# PG14__Ethernet.net
KiCad netlist of a schematic drawn in Altium Designer
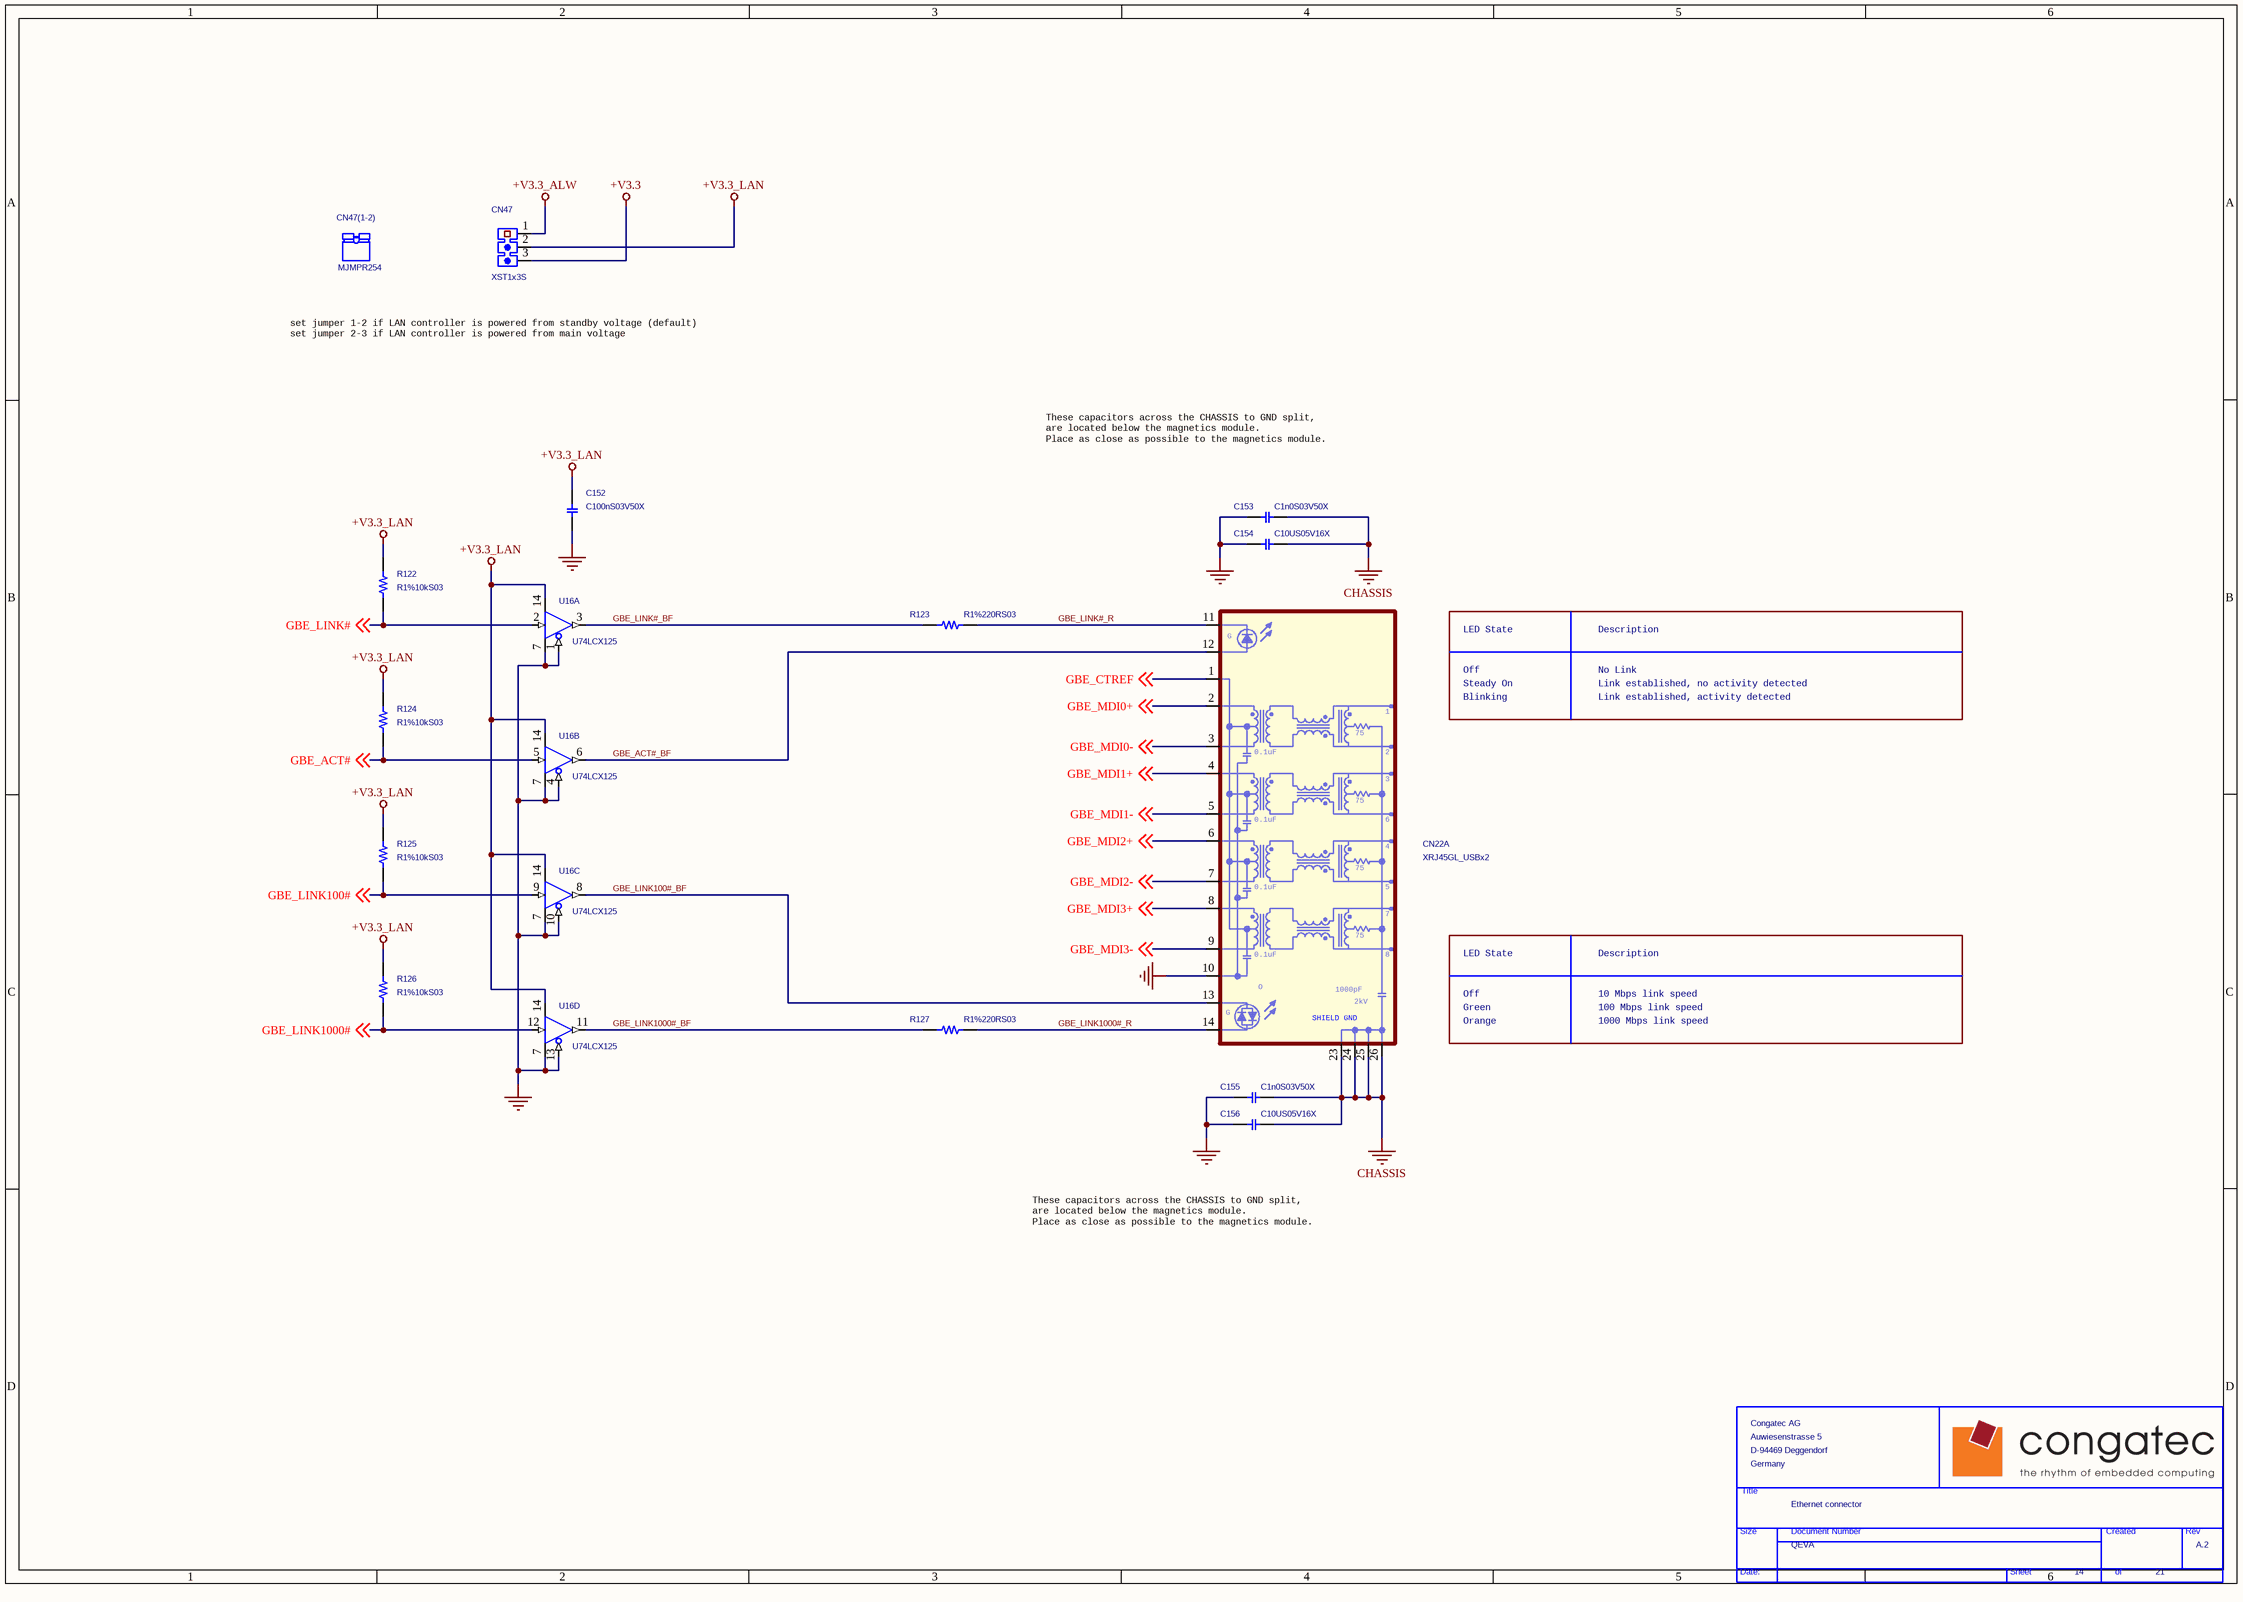
[diagram p0: PG14_ Ethernet.SchDoc]

(export (version "E")
  (design (tool "Eeschema 10.0.6"))
  (components
    (comp (ref "C152")
      (value "C100nS03V50X")
      (description "CAP 0.1U 50V +-10% SMD 0603 X7R WO/Pb")
      (fields
        (field (name "MANUFACTURE PART NUMBER") "C1608X7R1H104KT223858615649")
        (field (name "TOLERANCE") "10%")
      )
      (libsource (lib "*") (part "11_C_0"))
    )
    (comp (ref "C153")
      (value "C1n0S03V50X")
      (description "CAP 1000pF 50V 10% 0603 MLCC")
      (fields (field (name "PART NUMBER") "1124510290") (field (name "TOLERANCE") "10%"))
      (libsource (lib "*") (part "11_C_0"))
    )
    (comp (ref "C154")
      (value "C10US05V16X")
      (description "CAP 10u 6.3V +/-10% SMD 0805 MLCC X5R KEMET")
      (fields (field (name "MANUFACTURE PART NUMBER") "C0805C106K9PAC") (field (name "TOLERANCE") "10%"))
      (libsource (lib "*") (part "11_C_0"))
    )
    (comp (ref "C155")
      (value "C1n0S03V50X")
      (description "CAP 1000pF 50V 10% 0603 MLCC")
      (fields (field (name "PART NUMBER") "1124510290") (field (name "TOLERANCE") "10%"))
      (libsource (lib "*") (part "11_C_0"))
    )
    (comp (ref "C156")
      (value "C10US05V16X")
      (description "CAP 10u 6.3V +/-10% SMD 0805 MLCC X5R KEMET")
      (fields (field (name "MANUFACTURE PART NUMBER") "C0805C106K9PAC") (field (name "TOLERANCE") "10%"))
      (libsource (lib "*") (part "11_C_0"))
    )
    (comp (ref "CN22")
      (value "XRJ45GL_USBx2")
      (description "PhoneJack RJ45+USB*2 90D(F) W/LED&XFMR DIP")
      (fields (field (name "PART NUMBER") "165250820M") (field (name "PART_NUMBER") "41500328"))
      (libsource (lib "*") (part "1652_RJ45-P3515619W9_0"))
    )
    (comp (ref "CN47")
      (value "XST1x3S")
      (description "PIN HEADER 3*1P 180D(M) 2.54mm DIP WO/Pb")
      (fields
        (field (name "PART NUMBER") "1653003100")
        (field (name "MANUFACTURE PART NUMBER") "205-1x3GS RoHS1130-000-03S21N12564-03S10B-01G-6/3")
      )
      (libsource (lib "*") (part "1653_JH3X1V_0"))
    )
    (comp (ref "CN47(1-2)")
      (value "MJMPR254")
      (description "MINI JUMPER 2P 180D(F) 2.54mm DIP (yellow)")
      (fields
        (field (name "MANUFACTURE PART NUMBER") "1132-040-02HL0305302MJ1P-BG0L151-240-00000306")
        (field (name "PART NUMBER") "1653300100")
      )
      (libsource (lib "*") (part "1653_MINIJUMPER22.54MM_0"))
    )
    (comp (ref "R122")
      (value "R1%10kS03")
      (description "R 10K 1/10W 1% SMD 0603 CR WO/Pb")
      (fields (field (name "PART_NUMBER") "45502052") (field (name "PART NUMBER") "105A510023"))
      (libsource (lib "*") (part "10_R_0_Dup1"))
    )
    (comp (ref "R123")
      (value "R1%220RS03")
      (description "220 1/10W 5% 0603 CR WO/Pb")
      (fields
        (field (name "PART_NUMBER") "45502013")
        (field (name "MANUFACTURE PART NUMBER") "0603WAJ0221T5E232270260221LRM06JTN221")
      )
      (libsource (lib "*") (part "10_R_0_Dup1"))
    )
    (comp (ref "R124")
      (value "R1%10kS03")
      (description "R 10K 1/10W 1% SMD 0603 CR WO/Pb")
      (fields (field (name "PART_NUMBER") "45502052") (field (name "PART NUMBER") "105A510023"))
      (libsource (lib "*") (part "10_R_0_Dup1"))
    )
    (comp (ref "R125")
      (value "R1%10kS03")
      (description "R 10K 1/10W 1% SMD 0603 CR WO/Pb")
      (fields (field (name "PART_NUMBER") "45502052") (field (name "PART NUMBER") "105A510023"))
      (libsource (lib "*") (part "10_R_0_Dup1"))
    )
    (comp (ref "R126")
      (value "R1%10kS03")
      (description "R 10K 1/10W 1% SMD 0603 CR WO/Pb")
      (fields (field (name "PART_NUMBER") "45502052") (field (name "PART NUMBER") "105A510023"))
      (libsource (lib "*") (part "10_R_0_Dup1"))
    )
    (comp (ref "R127")
      (value "R1%220RS03")
      (description "220 1/10W 5% 0603 CR WO/Pb")
      (fields
        (field (name "MANUFACTURE PART NUMBER") "0603WAJ0221T5E232270260221LRM06JTN221")
        (field (name "TOLERANCE") "5%")
      )
      (libsource (lib "*") (part "10_R_0_Dup1"))
    )
    (comp (ref "U16")
      (value "U74LCX125")
      (description "IC SMD SN74LVC125ADT SOIC 14P TI")
      (fields
        (field (name "PART_NUMBER") "43000421")
        (field (name "MANUFACTURE PART NUMBER") "SN74LVC125ADT")
        (field (name "PART NUMBER") "14S5A12500")
      )
      (libsource (lib "*") (part "14S_TI_SN74LVC125ADT_SOIC14_1"))
    )
  )
  (nets
    (net (code "1") (name "+V3.3") (class "Default")
      (node (ref "CN47") (pin "3") (pinfunction "3_3") (pintype "passive"))
    )
    (net (code "2") (name "+V3.3_ALW") (class "Default")
      (node (ref "CN47") (pin "1") (pinfunction "1_1") (pintype "passive"))
    )
    (net (code "3") (name "+V3.3_LAN") (class "Default")
      (node (ref "C152") (pin "1") (pinfunction "1_1") (pintype "passive"))
      (node (ref "CN47") (pin "2") (pinfunction "2_2") (pintype "passive"))
      (node (ref "R122") (pin "1") (pinfunction "1_1") (pintype "passive"))
      (node (ref "R124") (pin "1") (pinfunction "1_1") (pintype "passive"))
      (node (ref "R125") (pin "1") (pinfunction "1_1") (pintype "passive"))
      (node (ref "R126") (pin "1") (pinfunction "1_1") (pintype "passive"))
      (node (ref "U16") (pin "14") (pinfunction "VCC_14") (pintype "power_in"))
    )
    (net (code "4") (name "/GBE_ACT#_BF") (class "Default")
      (node (ref "CN22") (pin "12") (pinfunction "ACT+_12") (pintype "passive"))
      (node (ref "U16") (pin "6") (pinfunction "2Y_6") (pintype "output"))
    )
    (net (code "5") (name "/GBE_LINK#_BF") (class "Default")
      (node (ref "R123") (pin "1") (pinfunction "1_1") (pintype "passive"))
      (node (ref "U16") (pin "3") (pinfunction "1Y_3") (pintype "output"))
    )
    (net (code "6") (name "/GBE_LINK#_R") (class "Default")
      (node (ref "CN22") (pin "11") (pinfunction "ACT-_11") (pintype "passive"))
      (node (ref "R123") (pin "2") (pinfunction "2_2") (pintype "passive"))
    )
    (net (code "7") (name "/GBE_LINK100#_BF") (class "Default")
      (node (ref "CN22") (pin "13") (pinfunction "LINK1_13") (pintype "passive"))
      (node (ref "U16") (pin "8") (pinfunction "3Y_8") (pintype "output"))
    )
    (net (code "8") (name "/GBE_LINK1000#_BF") (class "Default")
      (node (ref "R127") (pin "1") (pinfunction "1_1") (pintype "passive"))
      (node (ref "U16") (pin "11") (pinfunction "4Y_11") (pintype "output"))
    )
    (net (code "9") (name "/GBE_LINK1000#_R") (class "Default")
      (node (ref "CN22") (pin "14") (pinfunction "LINK2_14") (pintype "passive"))
      (node (ref "R127") (pin "2") (pinfunction "2_2") (pintype "passive"))
    )
    (net (code "10") (name "CHASSIS") (class "Default")
      (node (ref "C153") (pin "2") (pinfunction "2_2") (pintype "passive"))
      (node (ref "C154") (pin "2") (pinfunction "2_2") (pintype "passive"))
      (node (ref "C155") (pin "2") (pinfunction "2_2") (pintype "passive"))
      (node (ref "C156") (pin "2") (pinfunction "2_2") (pintype "passive"))
      (node (ref "CN22") (pin "23") (pinfunction "GND_1_23") (pintype "passive"))
      (node (ref "CN22") (pin "24") (pinfunction "GND_2_24") (pintype "passive"))
      (node (ref "CN22") (pin "25") (pinfunction "GND_3_25") (pintype "passive"))
      (node (ref "CN22") (pin "26") (pinfunction "GND_4_26") (pintype "passive"))
    )
    (net (code "11") (name "GBE_ACT#") (class "Default")
      (node (ref "R124") (pin "2") (pinfunction "2_2") (pintype "passive"))
      (node (ref "U16") (pin "5") (pinfunction "2A_5") (pintype "input"))
    )
    (net (code "12") (name "GBE_CTREF") (class "Default")
      (node (ref "CN22") (pin "1") (pinfunction "TCT1_1") (pintype "passive"))
    )
    (net (code "13") (name "GBE_LINK#") (class "Default")
      (node (ref "R122") (pin "2") (pinfunction "2_2") (pintype "passive"))
      (node (ref "U16") (pin "2") (pinfunction "1A_2") (pintype "input"))
    )
    (net (code "14") (name "GBE_LINK100#") (class "Default")
      (node (ref "R125") (pin "2") (pinfunction "2_2") (pintype "passive"))
      (node (ref "U16") (pin "9") (pinfunction "3A_9") (pintype "input"))
    )
    (net (code "15") (name "GBE_LINK1000#") (class "Default")
      (node (ref "R126") (pin "2") (pinfunction "2_2") (pintype "passive"))
      (node (ref "U16") (pin "12") (pinfunction "4A_12") (pintype "input"))
    )
    (net (code "16") (name "GBE_MDI0+") (class "Default")
      (node (ref "CN22") (pin "2") (pinfunction "0+_2") (pintype "passive"))
    )
    (net (code "17") (name "GBE_MDI0-") (class "Default")
      (node (ref "CN22") (pin "3") (pinfunction "0-_3") (pintype "passive"))
    )
    (net (code "18") (name "GBE_MDI1+") (class "Default")
      (node (ref "CN22") (pin "4") (pinfunction "1+_4") (pintype "passive"))
    )
    (net (code "19") (name "GBE_MDI1-") (class "Default")
      (node (ref "CN22") (pin "5") (pinfunction "1-_5") (pintype "passive"))
    )
    (net (code "20") (name "GBE_MDI2+") (class "Default")
      (node (ref "CN22") (pin "6") (pinfunction "2+_6") (pintype "passive"))
    )
    (net (code "21") (name "GBE_MDI2-") (class "Default")
      (node (ref "CN22") (pin "7") (pinfunction "2-_7") (pintype "passive"))
    )
    (net (code "22") (name "GBE_MDI3+") (class "Default")
      (node (ref "CN22") (pin "8") (pinfunction "3+_8") (pintype "passive"))
    )
    (net (code "23") (name "GBE_MDI3-") (class "Default")
      (node (ref "CN22") (pin "9") (pinfunction "3-_9") (pintype "passive"))
    )
    (net (code "24") (name "GND") (class "Default")
      (node (ref "C152") (pin "2") (pinfunction "2_2") (pintype "passive"))
      (node (ref "C153") (pin "1") (pinfunction "1_1") (pintype "passive"))
      (node (ref "C154") (pin "1") (pinfunction "1_1") (pintype "passive"))
      (node (ref "C155") (pin "1") (pinfunction "1_1") (pintype "passive"))
      (node (ref "C156") (pin "1") (pinfunction "1_1") (pintype "passive"))
      (node (ref "CN22") (pin "10") (pinfunction "TCT2_10") (pintype "passive"))
      (node (ref "U16") (pin "1") (pinfunction "1OE_1") (pintype "input"))
      (node (ref "U16") (pin "10") (pinfunction "3OE_10") (pintype "input"))
      (node (ref "U16") (pin "13") (pinfunction "4OE_13") (pintype "input"))
      (node (ref "U16") (pin "4") (pinfunction "2OE_4") (pintype "input"))
      (node (ref "U16") (pin "7") (pinfunction "GND_7") (pintype "power_in"))
    )
  )
)
